# dashbutton_2450_v4.net
KiCad netlist of a schematic drawn in EAGLE
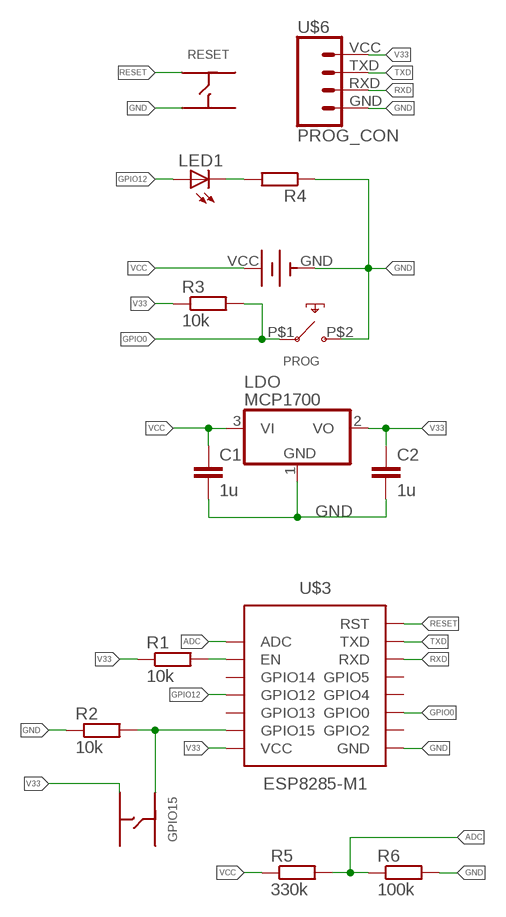
[diagram p0: schematic, sheet 1]

(export (version "E")
  (design (tool "Eeschema 10.0.6"))
  (components
    (comp (ref "C1")
      (value "1u")
      (footprint "eagle-import:C1206")
      (libsource (lib "eagle-import") (part "C-EUC1206"))
    )
    (comp (ref "C2")
      (value "1u")
      (footprint "eagle-import:C1206")
      (libsource (lib "eagle-import") (part "C-EUC1206"))
    )
    (comp (ref "GPIO15")
      (value "6X6BUTTON")
      (footprint "eagle-import:6X6BUTTON")
      (libsource (lib "eagle-import") (part "6X6BUTTON"))
    )
    (comp (ref "LDO")
      (value "MCP1700")
      (footprint "eagle-import:SOT23")
      (libsource (lib "eagle-import") (part "MCP1703CB"))
    )
    (comp (ref "LED1")
      (value "LEDCHIPLED_1206")
      (footprint "eagle-import:CHIPLED_1206")
      (libsource (lib "eagle-import") (part "LEDCHIPLED_1206"))
    )
    (comp (ref "PROG")
      (value "3X4_SMD_BUTTON")
      (footprint "eagle-import:3X4BUTTON")
      (libsource (lib "eagle-import") (part "3X4_SMD_BUTTON"))
    )
    (comp (ref "R1")
      (value "10k")
      (footprint "eagle-import:R0603")
      (libsource (lib "eagle-import") (part "R-EU_R0603"))
    )
    (comp (ref "R2")
      (value "10k")
      (footprint "eagle-import:R0603")
      (libsource (lib "eagle-import") (part "R-EU_R0603"))
    )
    (comp (ref "R3")
      (value "10k")
      (footprint "eagle-import:R0603")
      (libsource (lib "eagle-import") (part "R-EU_R0603"))
    )
    (comp (ref "R4")
      (value "R-EU_R1206")
      (footprint "eagle-import:R1206")
      (libsource (lib "eagle-import") (part "R-EU_R1206"))
    )
    (comp (ref "R5")
      (value "330k")
      (footprint "eagle-import:R0603")
      (libsource (lib "eagle-import") (part "R-EU_R0603"))
    )
    (comp (ref "R6")
      (value "100k")
      (footprint "eagle-import:R0603")
      (libsource (lib "eagle-import") (part "R-EU_R0603"))
    )
    (comp (ref "RESET")
      (value "6X6BUTTON")
      (footprint "eagle-import:6X6BUTTON")
      (libsource (lib "eagle-import") (part "6X6BUTTON"))
    )
    (comp (ref "U$2")
      (value "2450_BATTERYHOLDER_SMD")
      (footprint "eagle-import:2450_BATTERYHOLDER_SMD")
      (libsource (lib "eagle-import") (part "2450_BATTERYHOLDER_SMD"))
    )
    (comp (ref "U$3")
      (value "ESP8285-M1")
      (footprint "eagle-import:ESP8285-M1")
      (libsource (lib "eagle-import") (part "ESP8285-M1"))
    )
    (comp (ref "U$6")
      (value "PROG_CON")
      (footprint "eagle-import:PROG_CON")
      (libsource (lib "eagle-import") (part "PROG_CON"))
    )
  )
  (nets
    (net (code "1") (name "ADC") (class "Default")
      (node (ref "R5") (pin "2") (pinfunction "2_2") (pintype "passive"))
      (node (ref "R6") (pin "1") (pinfunction "1_1") (pintype "passive"))
      (node (ref "U$3") (pin "ADC") (pinfunction "ADC_ADC") (pintype "bidirectional"))
    )
    (net (code "2") (name "GND") (class "Default")
      (node (ref "C1") (pin "2") (pinfunction "2_2") (pintype "passive"))
      (node (ref "C2") (pin "2") (pinfunction "2_2") (pintype "passive"))
      (node (ref "LDO") (pin "1") (pinfunction "GND_1") (pintype "passive"))
      (node (ref "PROG") (pin "P$2") (pinfunction "P2_P$2") (pintype "bidirectional"))
      (node (ref "R2") (pin "1") (pinfunction "1_1") (pintype "passive"))
      (node (ref "R4") (pin "1") (pinfunction "1_1") (pintype "passive"))
      (node (ref "R6") (pin "2") (pinfunction "2_2") (pintype "passive"))
      (node (ref "RESET") (pin "P1") (pinfunction "A1_P1") (pintype "bidirectional"))
      (node (ref "U$2") (pin "GND") (pinfunction "GND_GND") (pintype "bidirectional"))
      (node (ref "U$3") (pin "GND") (pinfunction "GND_GND") (pintype "bidirectional"))
      (node (ref "U$6") (pin "GND") (pinfunction "1_GND") (pintype "passive"))
    )
    (net (code "3") (name "GPIO0") (class "Default")
      (node (ref "PROG") (pin "P$1") (pinfunction "P1_P$1") (pintype "bidirectional"))
      (node (ref "R3") (pin "2") (pinfunction "2_2") (pintype "passive"))
      (node (ref "U$3") (pin "GPIO0") (pinfunction "GPIO0_GPIO0") (pintype "bidirectional"))
    )
    (net (code "4") (name "GPIO12") (class "Default")
      (node (ref "LED1") (pin "A") (pinfunction "A_A") (pintype "passive"))
      (node (ref "U$3") (pin "GPIO12") (pinfunction "GPIO12_GPIO12") (pintype "bidirectional"))
    )
    (net (code "5") (name "Net-(GPIO15-U2)") (class "Default")
      (node (ref "GPIO15") (pin "P4") (pinfunction "U2_P4") (pintype "bidirectional"))
      (node (ref "R2") (pin "2") (pinfunction "2_2") (pintype "passive"))
      (node (ref "U$3") (pin "GPIO15") (pinfunction "GPIO15_GPIO15") (pintype "bidirectional"))
    )
    (net (code "6") (name "Net-(LED1-PadC)") (class "Default")
      (node (ref "LED1") (pin "C") (pinfunction "C_C") (pintype "passive"))
      (node (ref "R4") (pin "2") (pinfunction "2_2") (pintype "passive"))
    )
    (net (code "7") (name "Net-(R1-Pad2)") (class "Default")
      (node (ref "R1") (pin "2") (pinfunction "2_2") (pintype "passive"))
      (node (ref "U$3") (pin "EN") (pinfunction "EN_EN") (pintype "bidirectional"))
    )
    (net (code "8") (name "RESET") (class "Default")
      (node (ref "RESET") (pin "P3") (pinfunction "U1_P3") (pintype "bidirectional"))
      (node (ref "U$3") (pin "RST") (pinfunction "RST_RST") (pintype "bidirectional"))
    )
    (net (code "9") (name "RXD") (class "Default")
      (node (ref "U$3") (pin "RXD") (pinfunction "RXD_RXD") (pintype "bidirectional"))
      (node (ref "U$6") (pin "RXD") (pinfunction "2_RXD") (pintype "passive"))
    )
    (net (code "10") (name "TXD") (class "Default")
      (node (ref "U$3") (pin "TXD") (pinfunction "TXD_TXD") (pintype "bidirectional"))
      (node (ref "U$6") (pin "TXD") (pinfunction "3_TXD") (pintype "passive"))
    )
    (net (code "11") (name "V33") (class "Default")
      (node (ref "C2") (pin "1") (pinfunction "1_1") (pintype "passive"))
      (node (ref "GPIO15") (pin "P2") (pinfunction "A2_P2") (pintype "bidirectional"))
      (node (ref "LDO") (pin "2") (pinfunction "VO_2") (pintype "passive"))
      (node (ref "R1") (pin "1") (pinfunction "1_1") (pintype "passive"))
      (node (ref "R3") (pin "1") (pinfunction "1_1") (pintype "passive"))
      (node (ref "U$3") (pin "V33") (pinfunction "VCC_V33") (pintype "bidirectional"))
      (node (ref "U$6") (pin "VCC") (pinfunction "4_VCC") (pintype "passive"))
    )
    (net (code "12") (name "VCC") (class "Default")
      (node (ref "C1") (pin "1") (pinfunction "1_1") (pintype "passive"))
      (node (ref "LDO") (pin "3") (pinfunction "VI_3") (pintype "input"))
      (node (ref "R5") (pin "1") (pinfunction "1_1") (pintype "passive"))
      (node (ref "U$2") (pin "VCC") (pinfunction "VCC_VCC") (pintype "bidirectional"))
    )
    (net (code "13") (name "unconnected-(GPIO15-A1-PadP1)") (class "Default")
      (node (ref "GPIO15") (pin "P1") (pinfunction "A1_P1") (pintype "bidirectional"))
    )
    (net (code "14") (name "unconnected-(GPIO15-U1-PadP3)") (class "Default")
      (node (ref "GPIO15") (pin "P3") (pinfunction "U1_P3") (pintype "bidirectional"))
    )
    (net (code "15") (name "unconnected-(RESET-A2-PadP2)") (class "Default")
      (node (ref "RESET") (pin "P2") (pinfunction "A2_P2") (pintype "bidirectional"))
    )
    (net (code "16") (name "unconnected-(RESET-U2-PadP4)") (class "Default")
      (node (ref "RESET") (pin "P4") (pinfunction "U2_P4") (pintype "bidirectional"))
    )
    (net (code "17") (name "unconnected-(U$3-PadGPIO2)") (class "Default")
      (node (ref "U$3") (pin "GPIO2") (pinfunction "GPIO2_GPIO2") (pintype "bidirectional"))
    )
    (net (code "18") (name "unconnected-(U$3-PadGPIO4)") (class "Default")
      (node (ref "U$3") (pin "GPIO4") (pinfunction "GPIO4_GPIO4") (pintype "bidirectional"))
    )
    (net (code "19") (name "unconnected-(U$3-PadGPIO5)") (class "Default")
      (node (ref "U$3") (pin "GPIO5") (pinfunction "GPIO5_GPIO5") (pintype "bidirectional"))
    )
    (net (code "20") (name "unconnected-(U$3-PadGPIO13)") (class "Default")
      (node (ref "U$3") (pin "GPIO13") (pinfunction "GPIO13_GPIO13") (pintype "bidirectional"))
    )
    (net (code "21") (name "unconnected-(U$3-PadGPIO14)") (class "Default")
      (node (ref "U$3") (pin "GPIO14") (pinfunction "GPIO14_GPIO14") (pintype "bidirectional"))
    )
  )
)
